# TM4C123GH6PM_1.net
KiCad netlist of a schematic drawn in Altium Designer
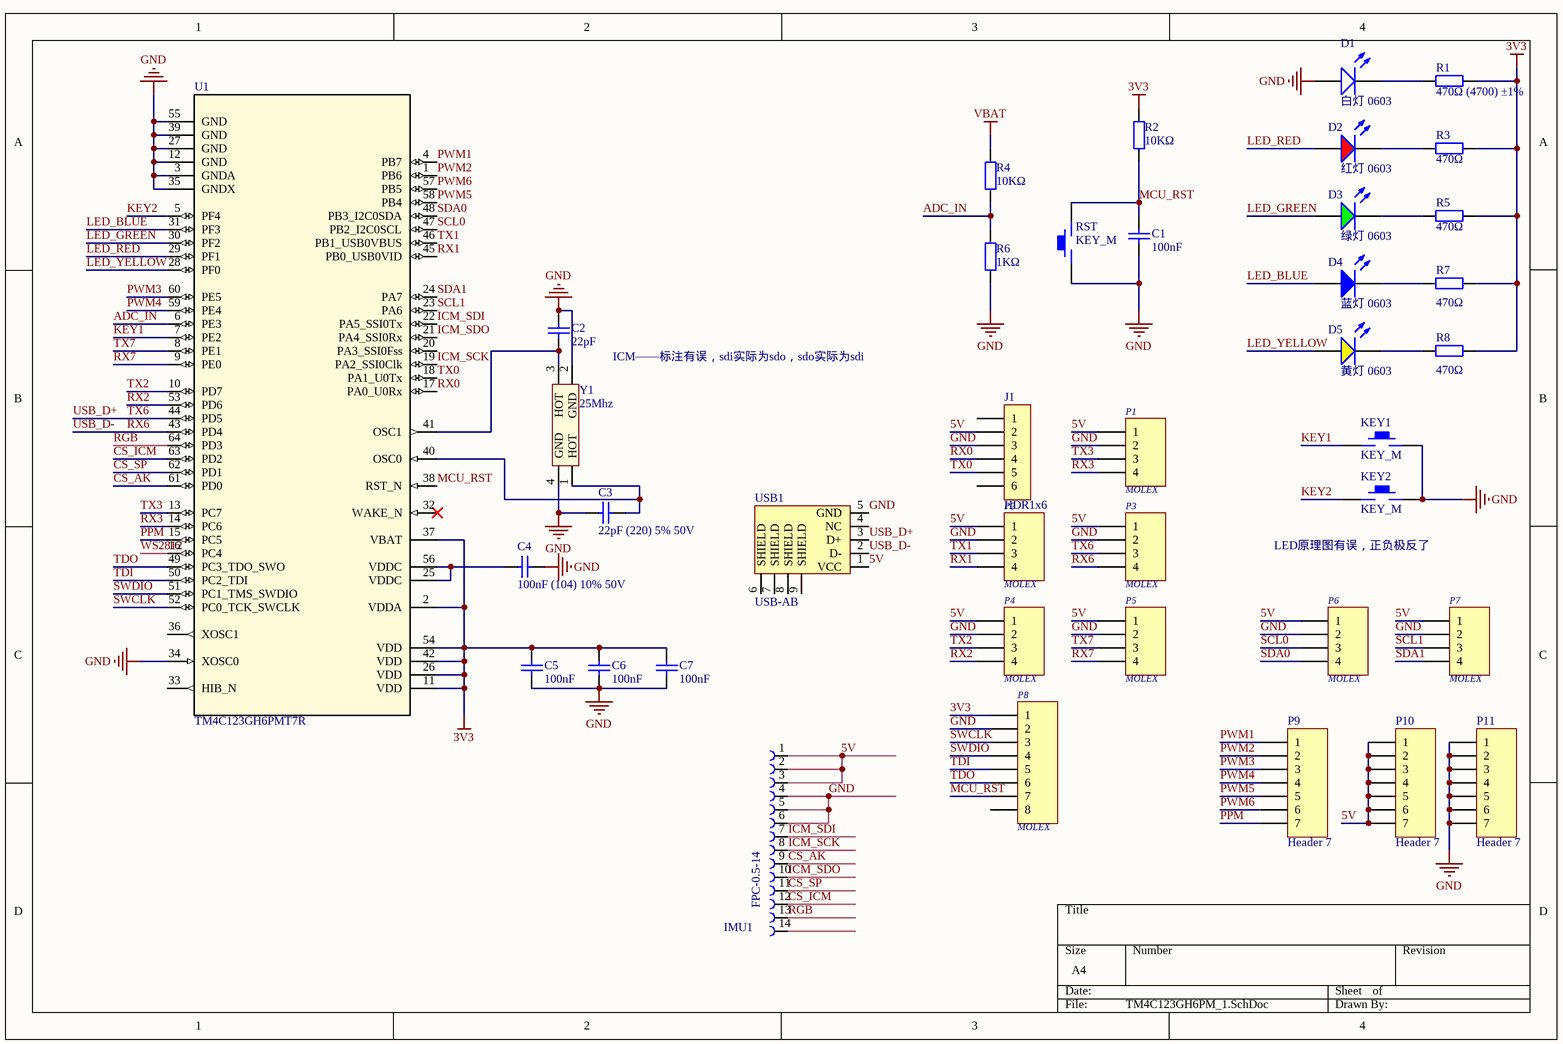
[diagram p0: TM4C123GH6PM_1.SchDoc]

(export (version "E")
  (design (tool "Eeschema 10.0.6"))
  (components
    (comp (ref "C1")
      (value "100nF")
      (footprint "0603_C")
      (description "贴片电容")
      (libsource (lib "Miscellaneous Devices LC") (part "0603 100nF (104) 10% 50V"))
    )
    (comp (ref "C2")
      (value "22pF")
      (footprint "0603_C")
      (description "贴片电容")
      (libsource (lib "Miscellaneous Devices LC") (part "0603 22pF (220) 5% 50V"))
    )
    (comp (ref "C3")
      (value "22pF (220) 5% 50V")
      (footprint "0603_C")
      (description "贴片电容")
      (libsource (lib "Miscellaneous Devices LC") (part "0603 22pF (220) 5% 50V"))
    )
    (comp (ref "C4")
      (value "100nF (104) 10% 50V")
      (footprint "0603_C")
      (description "贴片电容")
      (libsource (lib "Miscellaneous Devices LC") (part "0603 100nF (104) 10% 50V"))
    )
    (comp (ref "C5")
      (value "100nF")
      (footprint "0603_C")
      (description "贴片电容")
      (libsource (lib "Miscellaneous Devices LC") (part "0603 100nF (104) 10% 50V"))
    )
    (comp (ref "C6")
      (value "100nF")
      (footprint "0603_C")
      (description "贴片电容")
      (libsource (lib "Miscellaneous Devices LC") (part "0603 100nF (104) 10% 50V"))
    )
    (comp (ref "C7")
      (value "100nF")
      (footprint "0603_C")
      (description "贴片电容")
      (libsource (lib "Miscellaneous Devices LC") (part "0603 100nF (104) 10% 50V"))
    )
    (comp (ref "D1")
      (value "白灯 0603")
      (footprint "0603_LED_S1")
      (description "发光二极管")
      (libsource (lib "Miscellaneous Devices LC") (part "0603 白灯"))
    )
    (comp (ref "D2")
      (value "红灯 0603")
      (footprint "0603_LED_S1")
      (description "发光二极管")
      (libsource (lib "Miscellaneous Devices LC") (part "0603 红灯"))
    )
    (comp (ref "D3")
      (value "绿灯 0603")
      (footprint "0603_LED_S1")
      (description "发光二极管")
      (libsource (lib "Miscellaneous Devices LC") (part "0603 绿灯"))
    )
    (comp (ref "D4")
      (value "蓝灯 0603")
      (footprint "0603_LED_S1")
      (description "发光二极管")
      (libsource (lib "Miscellaneous Devices LC") (part "0603 蓝灯"))
    )
    (comp (ref "D5")
      (value "黄灯 0603")
      (footprint "0603_LED_S1")
      (description "发光二极管")
      (libsource (lib "Miscellaneous Devices LC") (part "0603 黄灯"))
    )
    (comp (ref "IMU1")
      (value "FPC-0.5-14")
      (footprint "FPC-0.5-14")
      (description "FFC / FPC Board Connector, WR-FPC Series, Surface Mount, Receptacle, 14, Bottom, 0.5 mm")
      (fields (field (name "MP") "687114149022") (field (name "MF") "Wurth Electronics"))
      (libsource (lib "MyLib") (part "FPC-0.5-14"))
    )
    (comp (ref "J1")
      (value "HDR1x6")
      (footprint "PIN-6-2.54-1.0")
      (description "Connector")
      (libsource (lib "MyLib") (part "HDR1x6"))
    )
    (comp (ref "KEY1")
      (value "KEY_M")
      (footprint "KEY_SOP3625")
      (libsource (lib "STM32F767核心板封装库") (part "KEY_M"))
    )
    (comp (ref "KEY2")
      (value "KEY_M")
      (footprint "KEY_SOP3625")
      (libsource (lib "STM32F767核心板封装库") (part "KEY_M"))
    )
    (comp (ref "P1")
      (value "MOLEX")
      (footprint "1.25 molex")
      (fields (field (name "PUBLISHER") "Altium Limited"))
      (libsource (lib "fly_smart") (part "Header 4"))
    )
    (comp (ref "P2")
      (value "MOLEX")
      (footprint "1.25 molex")
      (fields (field (name "PUBLISHER") "Altium Limited"))
      (libsource (lib "fly_smart") (part "Header 4"))
    )
    (comp (ref "P3")
      (value "MOLEX")
      (footprint "1.25 molex")
      (fields (field (name "PUBLISHER") "Altium Limited"))
      (libsource (lib "fly_smart") (part "Header 4"))
    )
    (comp (ref "P4")
      (value "MOLEX")
      (footprint "1.25 molex")
      (fields (field (name "PUBLISHER") "Altium Limited"))
      (libsource (lib "fly_smart") (part "Header 4"))
    )
    (comp (ref "P5")
      (value "MOLEX")
      (footprint "1.25 molex")
      (fields (field (name "PUBLISHER") "Altium Limited"))
      (libsource (lib "fly_smart") (part "Header 4"))
    )
    (comp (ref "P6")
      (value "MOLEX")
      (footprint "1.25 molex")
      (fields (field (name "PUBLISHER") "Altium Limited"))
      (libsource (lib "fly_smart") (part "Header 4"))
    )
    (comp (ref "P7")
      (value "MOLEX")
      (footprint "1.25 molex")
      (fields (field (name "PUBLISHER") "Altium Limited"))
      (libsource (lib "fly_smart") (part "Header 4"))
    )
    (comp (ref "P8")
      (value "MOLEX")
      (footprint "1.25 molex -8")
      (fields (field (name "PUBLISHER") "Altium Limited"))
      (libsource (lib "TM4C_Series") (part "Header 8"))
    )
    (comp (ref "P9")
      (value "Header 7")
      (footprint "HDR1X7")
      (description "Header, 7-Pin")
      (fields (field (name "PUBLISHER") "Altium Limited"))
      (libsource (lib "Miscellaneous Connectors") (part "Header 7"))
    )
    (comp (ref "P10")
      (value "Header 7")
      (footprint "HDR1X7")
      (description "Header, 7-Pin")
      (fields (field (name "PUBLISHER") "Altium Limited"))
      (libsource (lib "Miscellaneous Connectors") (part "Header 7"))
    )
    (comp (ref "P11")
      (value "Header 7")
      (footprint "HDR1X7")
      (description "Header, 7-Pin")
      (fields (field (name "PUBLISHER") "Altium Limited"))
      (libsource (lib "Miscellaneous Connectors") (part "Header 7"))
    )
    (comp (ref "R1")
      (value "470Ω (4700) ±1%")
      (footprint "0603_R")
      (description "贴片电阻")
      (libsource (lib "Miscellaneous Devices LC") (part "0603 470Ω (4700) 1%"))
    )
    (comp (ref "R2")
      (value "10KΩ")
      (footprint "0603_R")
      (description "贴片电阻")
      (libsource (lib "Miscellaneous Devices LC") (part "0603 10KΩ (1002) 1%"))
    )
    (comp (ref "R3")
      (value "470Ω")
      (footprint "0603_R")
      (description "贴片电阻")
      (libsource (lib "Miscellaneous Devices LC") (part "0603 470Ω (4700) 1%"))
    )
    (comp (ref "R4")
      (value "10KΩ")
      (footprint "0603_R")
      (description "贴片电阻")
      (libsource (lib "Miscellaneous Devices LC") (part "0603 10KΩ (1002) 1%"))
    )
    (comp (ref "R5")
      (value "470Ω")
      (footprint "0603_R")
      (description "贴片电阻")
      (libsource (lib "Miscellaneous Devices LC") (part "0603 470Ω (4700) 1%"))
    )
    (comp (ref "R6")
      (value "1KΩ")
      (footprint "0603_R")
      (description "贴片电阻")
      (libsource (lib "Miscellaneous Devices LC") (part "0603 1KΩ (1001) 1%"))
    )
    (comp (ref "R7")
      (value "470Ω")
      (footprint "0603_R")
      (description "贴片电阻")
      (libsource (lib "Miscellaneous Devices LC") (part "0603 470Ω (4700) 1%"))
    )
    (comp (ref "R8")
      (value "470Ω")
      (footprint "0603_R")
      (description "贴片电阻")
      (libsource (lib "Miscellaneous Devices LC") (part "0603 470Ω (4700) 1%"))
    )
    (comp (ref "RST") (value "KEY_M") (footprint "KEY_SOP3625") (libsource (lib "") (part "KEY_M_1")))
    (comp (ref "U1")
      (value "TM4C123GH6PMT7R")
      (footprint "PM0064A_M")
      (description "Imported")
      (fields
        (field (name "PARTNUMBER") "TM4C123GH6PMTR")
        (field (name "ALTERNATE_PARTNUMBER") "TM4C123GH6PMT")
      )
      (libsource (lib "TM4C123GH6PM") (part "TM4C123GH6PMT7R"))
    )
    (comp (ref "USB1")
      (value "USB-AB")
      (footprint "USB_AB - 5S - B")
      (description "MicroUSB")
      (libsource (lib "TM4C_Series") (part "USB-AB"))
    )
    (comp (ref "Y1")
      (value "25Mhz")
      (footprint "XTAL3225")
      (description "3225贴片无源晶振")
      (libsource (lib "TM4C123GH6PM") (part "XTAL_3225"))
    )
  )
  (nets
    (net (code "1") (name "/5V") (class "Default")
      (node (ref "IMU1") (pin "1") (pinfunction "14_1") (pintype "passive"))
      (node (ref "IMU1") (pin "2") (pinfunction "13_2") (pintype "passive"))
      (node (ref "IMU1") (pin "3") (pinfunction "12_3") (pintype "passive"))
      (node (ref "J1") (pin "2") (pinfunction "2_2") (pintype "passive"))
      (node (ref "P1") (pin "1") (pinfunction "1_1") (pintype "passive"))
      (node (ref "P10") (pin "1") (pinfunction "1_1") (pintype "passive"))
      (node (ref "P10") (pin "2") (pinfunction "2_2") (pintype "passive"))
      (node (ref "P10") (pin "3") (pinfunction "3_3") (pintype "passive"))
      (node (ref "P10") (pin "4") (pinfunction "4_4") (pintype "passive"))
      (node (ref "P10") (pin "5") (pinfunction "5_5") (pintype "passive"))
      (node (ref "P10") (pin "6") (pinfunction "6_6") (pintype "passive"))
      (node (ref "P10") (pin "7") (pinfunction "7_7") (pintype "passive"))
      (node (ref "P2") (pin "1") (pinfunction "1_1") (pintype "passive"))
      (node (ref "P3") (pin "1") (pinfunction "1_1") (pintype "passive"))
      (node (ref "P4") (pin "1") (pinfunction "1_1") (pintype "passive"))
      (node (ref "P5") (pin "1") (pinfunction "1_1") (pintype "passive"))
      (node (ref "P6") (pin "1") (pinfunction "1_1") (pintype "passive"))
      (node (ref "P7") (pin "1") (pinfunction "1_1") (pintype "passive"))
      (node (ref "USB1") (pin "1") (pinfunction "VCC_1") (pintype "passive"))
    )
    (net (code "2") (name "/ADC_IN") (class "Default")
      (node (ref "R4") (pin "1") (pinfunction "1_1") (pintype "passive"))
      (node (ref "R6") (pin "2") (pinfunction "2_2") (pintype "passive"))
      (node (ref "U1") (pin "6") (pinfunction "PE3_6") (pintype "bidirectional"))
    )
    (net (code "3") (name "/CS_AK") (class "Default")
      (node (ref "IMU1") (pin "9") (pinfunction "6_9") (pintype "passive"))
      (node (ref "U1") (pin "61") (pinfunction "PD0_61") (pintype "bidirectional"))
    )
    (net (code "4") (name "/CS_ICM") (class "Default")
      (node (ref "IMU1") (pin "12") (pinfunction "3_12") (pintype "passive"))
      (node (ref "U1") (pin "63") (pinfunction "PD2_63") (pintype "bidirectional"))
    )
    (net (code "5") (name "/CS_SP") (class "Default")
      (node (ref "IMU1") (pin "11") (pinfunction "4_11") (pintype "passive"))
      (node (ref "U1") (pin "62") (pinfunction "PD1_62") (pintype "bidirectional"))
    )
    (net (code "6") (name "/ICM_SCK") (class "Default")
      (node (ref "IMU1") (pin "8") (pinfunction "7_8") (pintype "passive"))
      (node (ref "U1") (pin "19") (pinfunction "PA2_SSI0Clk_19") (pintype "bidirectional"))
    )
    (net (code "7") (name "/ICM_SDI") (class "Default")
      (node (ref "IMU1") (pin "7") (pinfunction "8_7") (pintype "passive"))
      (node (ref "U1") (pin "22") (pinfunction "PA5_SSI0Tx_22") (pintype "bidirectional"))
    )
    (net (code "8") (name "/ICM_SDO") (class "Default")
      (node (ref "IMU1") (pin "10") (pinfunction "5_10") (pintype "passive"))
      (node (ref "U1") (pin "21") (pinfunction "PA4_SSI0Rx_21") (pintype "bidirectional"))
    )
    (net (code "9") (name "/KEY1") (class "Default")
      (node (ref "KEY1") (pin "1") (pinfunction "1_1") (pintype "passive"))
      (node (ref "U1") (pin "7") (pinfunction "PE2_7") (pintype "bidirectional"))
    )
    (net (code "10") (name "/KEY2") (class "Default")
      (node (ref "KEY2") (pin "1") (pinfunction "1_1") (pintype "passive"))
      (node (ref "U1") (pin "5") (pinfunction "PF4_5") (pintype "bidirectional"))
    )
    (net (code "11") (name "/LED_BLUE") (class "Default")
      (node (ref "D4") (pin "A") (pinfunction "A_A") (pintype "passive"))
      (node (ref "U1") (pin "31") (pinfunction "PF3_31") (pintype "bidirectional"))
    )
    (net (code "12") (name "/LED_GREEN") (class "Default")
      (node (ref "D3") (pin "A") (pinfunction "A_A") (pintype "passive"))
      (node (ref "U1") (pin "30") (pinfunction "PF2_30") (pintype "bidirectional"))
    )
    (net (code "13") (name "/LED_RED") (class "Default")
      (node (ref "D2") (pin "A") (pinfunction "A_A") (pintype "passive"))
      (node (ref "U1") (pin "29") (pinfunction "PF1_29") (pintype "bidirectional"))
    )
    (net (code "14") (name "/LED_YELLOW") (class "Default")
      (node (ref "D5") (pin "A") (pinfunction "A_A") (pintype "passive"))
      (node (ref "U1") (pin "28") (pinfunction "PF0_28") (pintype "bidirectional"))
    )
    (net (code "15") (name "/MCU_RST") (class "Default")
      (node (ref "C1") (pin "2") (pinfunction "2_2") (pintype "passive"))
      (node (ref "P8") (pin "7") (pinfunction "7_7") (pintype "passive"))
      (node (ref "R2") (pin "1") (pinfunction "1_1") (pintype "passive"))
      (node (ref "RST") (pin "2") (pinfunction "2_2") (pintype "passive"))
      (node (ref "U1") (pin "38") (pinfunction "RST_N_38") (pintype "input"))
    )
    (net (code "16") (name "/PPM") (class "Default")
      (node (ref "P9") (pin "7") (pinfunction "7_7") (pintype "passive"))
      (node (ref "U1") (pin "15") (pinfunction "PC5_15") (pintype "bidirectional"))
    )
    (net (code "17") (name "/PWM1") (class "Default")
      (node (ref "P9") (pin "1") (pinfunction "1_1") (pintype "passive"))
      (node (ref "U1") (pin "4") (pinfunction "PB7_4") (pintype "bidirectional"))
    )
    (net (code "18") (name "/PWM2") (class "Default")
      (node (ref "P9") (pin "2") (pinfunction "2_2") (pintype "passive"))
      (node (ref "U1") (pin "1") (pinfunction "PB6_1") (pintype "bidirectional"))
    )
    (net (code "19") (name "/PWM3") (class "Default")
      (node (ref "P9") (pin "3") (pinfunction "3_3") (pintype "passive"))
      (node (ref "U1") (pin "60") (pinfunction "PE5_60") (pintype "bidirectional"))
    )
    (net (code "20") (name "/PWM4") (class "Default")
      (node (ref "P9") (pin "4") (pinfunction "4_4") (pintype "passive"))
      (node (ref "U1") (pin "59") (pinfunction "PE4_59") (pintype "bidirectional"))
    )
    (net (code "21") (name "/PWM5") (class "Default")
      (node (ref "P9") (pin "5") (pinfunction "5_5") (pintype "passive"))
      (node (ref "U1") (pin "58") (pinfunction "PB4_58") (pintype "bidirectional"))
    )
    (net (code "22") (name "/PWM6") (class "Default")
      (node (ref "P9") (pin "6") (pinfunction "6_6") (pintype "passive"))
      (node (ref "U1") (pin "57") (pinfunction "PB5_57") (pintype "bidirectional"))
    )
    (net (code "23") (name "/RGB") (class "Default")
      (node (ref "IMU1") (pin "13") (pinfunction "2_13") (pintype "passive"))
      (node (ref "U1") (pin "64") (pinfunction "PD3_64") (pintype "bidirectional"))
    )
    (net (code "24") (name "/RX0") (class "Default")
      (node (ref "J1") (pin "4") (pinfunction "4_4") (pintype "passive"))
      (node (ref "U1") (pin "17") (pinfunction "PA0_U0Rx_17") (pintype "bidirectional"))
    )
    (net (code "25") (name "/RX1") (class "Default")
      (node (ref "P2") (pin "4") (pinfunction "4_4") (pintype "passive"))
      (node (ref "U1") (pin "45") (pinfunction "PB0_USB0VID_45") (pintype "bidirectional"))
    )
    (net (code "26") (name "/RX2") (class "Default")
      (node (ref "P4") (pin "4") (pinfunction "4_4") (pintype "passive"))
      (node (ref "U1") (pin "53") (pinfunction "PD6_53") (pintype "bidirectional"))
    )
    (net (code "27") (name "/RX3") (class "Default")
      (node (ref "P1") (pin "4") (pinfunction "4_4") (pintype "passive"))
      (node (ref "U1") (pin "14") (pinfunction "PC6_14") (pintype "bidirectional"))
    )
    (net (code "28") (name "/RX6") (class "Default")
      (node (ref "P3") (pin "4") (pinfunction "4_4") (pintype "passive"))
      (node (ref "U1") (pin "43") (pinfunction "PD4_43") (pintype "bidirectional"))
      (node (ref "USB1") (pin "2") (pinfunction "D-_2") (pintype "passive"))
    )
    (net (code "29") (name "/RX7") (class "Default")
      (node (ref "P5") (pin "4") (pinfunction "4_4") (pintype "passive"))
      (node (ref "U1") (pin "9") (pinfunction "PE0_9") (pintype "bidirectional"))
    )
    (net (code "30") (name "/SCL0") (class "Default")
      (node (ref "P6") (pin "3") (pinfunction "3_3") (pintype "passive"))
      (node (ref "U1") (pin "47") (pinfunction "PB2_I2C0SCL_47") (pintype "bidirectional"))
    )
    (net (code "31") (name "/SCL1") (class "Default")
      (node (ref "P7") (pin "3") (pinfunction "3_3") (pintype "passive"))
      (node (ref "U1") (pin "23") (pinfunction "PA6_23") (pintype "bidirectional"))
    )
    (net (code "32") (name "/SDA0") (class "Default")
      (node (ref "P6") (pin "4") (pinfunction "4_4") (pintype "passive"))
      (node (ref "U1") (pin "48") (pinfunction "PB3_I2C0SDA_48") (pintype "bidirectional"))
    )
    (net (code "33") (name "/SDA1") (class "Default")
      (node (ref "P7") (pin "4") (pinfunction "4_4") (pintype "passive"))
      (node (ref "U1") (pin "24") (pinfunction "PA7_24") (pintype "bidirectional"))
    )
    (net (code "34") (name "/SWCLK") (class "Default")
      (node (ref "P8") (pin "3") (pinfunction "3_3") (pintype "passive"))
      (node (ref "U1") (pin "52") (pinfunction "PC0_TCK_SWCLK_52") (pintype "bidirectional"))
    )
    (net (code "35") (name "/SWDIO") (class "Default")
      (node (ref "P8") (pin "4") (pinfunction "4_4") (pintype "passive"))
      (node (ref "U1") (pin "51") (pinfunction "PC1_TMS_SWDIO_51") (pintype "bidirectional"))
    )
    (net (code "36") (name "/TDI") (class "Default")
      (node (ref "P8") (pin "5") (pinfunction "5_5") (pintype "passive"))
      (node (ref "U1") (pin "50") (pinfunction "PC2_TDI_50") (pintype "bidirectional"))
    )
    (net (code "37") (name "/TDO") (class "Default")
      (node (ref "P8") (pin "6") (pinfunction "6_6") (pintype "passive"))
      (node (ref "U1") (pin "49") (pinfunction "PC3_TDO_SWO_49") (pintype "bidirectional"))
    )
    (net (code "38") (name "/TX0") (class "Default")
      (node (ref "J1") (pin "5") (pinfunction "5_5") (pintype "passive"))
      (node (ref "U1") (pin "18") (pinfunction "PA1_U0Tx_18") (pintype "bidirectional"))
    )
    (net (code "39") (name "/TX1") (class "Default")
      (node (ref "P2") (pin "3") (pinfunction "3_3") (pintype "passive"))
      (node (ref "U1") (pin "46") (pinfunction "PB1_USB0VBUS_46") (pintype "bidirectional"))
    )
    (net (code "40") (name "/TX2") (class "Default")
      (node (ref "P4") (pin "3") (pinfunction "3_3") (pintype "passive"))
      (node (ref "U1") (pin "10") (pinfunction "PD7_10") (pintype "bidirectional"))
    )
    (net (code "41") (name "/TX3") (class "Default")
      (node (ref "P1") (pin "3") (pinfunction "3_3") (pintype "passive"))
      (node (ref "U1") (pin "13") (pinfunction "PC7_13") (pintype "bidirectional"))
    )
    (net (code "42") (name "/TX6") (class "Default")
      (node (ref "P3") (pin "3") (pinfunction "3_3") (pintype "passive"))
      (node (ref "U1") (pin "44") (pinfunction "PD5_44") (pintype "bidirectional"))
      (node (ref "USB1") (pin "3") (pinfunction "D+_3") (pintype "passive"))
    )
    (net (code "43") (name "/TX7") (class "Default")
      (node (ref "P5") (pin "3") (pinfunction "3_3") (pintype "passive"))
      (node (ref "U1") (pin "8") (pinfunction "PE1_8") (pintype "bidirectional"))
    )
    (net (code "44") (name "/WS2812") (class "Default")
      (node (ref "U1") (pin "16") (pinfunction "PC4_16") (pintype "bidirectional"))
    )
    (net (code "45") (name "3V3") (class "Default")
      (node (ref "C5") (pin "2") (pinfunction "2_2") (pintype "passive"))
      (node (ref "C6") (pin "2") (pinfunction "2_2") (pintype "passive"))
      (node (ref "C7") (pin "2") (pinfunction "2_2") (pintype "passive"))
      (node (ref "P8") (pin "1") (pinfunction "1_1") (pintype "passive"))
      (node (ref "R1") (pin "2") (pinfunction "2_2") (pintype "passive"))
      (node (ref "R2") (pin "2") (pinfunction "2_2") (pintype "passive"))
      (node (ref "R3") (pin "2") (pinfunction "2_2") (pintype "passive"))
      (node (ref "R5") (pin "2") (pinfunction "2_2") (pintype "passive"))
      (node (ref "R7") (pin "2") (pinfunction "2_2") (pintype "passive"))
      (node (ref "R8") (pin "2") (pinfunction "2_2") (pintype "passive"))
      (node (ref "U1") (pin "11") (pinfunction "VDD_11") (pintype "power_in"))
      (node (ref "U1") (pin "2") (pinfunction "VDDA_2") (pintype "power_in"))
      (node (ref "U1") (pin "26") (pinfunction "VDD_26") (pintype "power_in"))
      (node (ref "U1") (pin "37") (pinfunction "VBAT_37") (pintype "power_in"))
      (node (ref "U1") (pin "42") (pinfunction "VDD_42") (pintype "power_in"))
      (node (ref "U1") (pin "54") (pinfunction "VDD_54") (pintype "power_in"))
    )
    (net (code "46") (name "GND") (class "Default")
      (node (ref "C1") (pin "1") (pinfunction "1_1") (pintype "passive"))
      (node (ref "C2") (pin "2") (pinfunction "2_2") (pintype "passive"))
      (node (ref "C3") (pin "2") (pinfunction "2_2") (pintype "passive"))
      (node (ref "C4") (pin "2") (pinfunction "2_2") (pintype "passive"))
      (node (ref "C5") (pin "1") (pinfunction "1_1") (pintype "passive"))
      (node (ref "C6") (pin "1") (pinfunction "1_1") (pintype "passive"))
      (node (ref "C7") (pin "1") (pinfunction "1_1") (pintype "passive"))
      (node (ref "D1") (pin "A") (pinfunction "A_A") (pintype "passive"))
      (node (ref "IMU1") (pin "4") (pinfunction "11_4") (pintype "passive"))
      (node (ref "IMU1") (pin "5") (pinfunction "10_5") (pintype "passive"))
      (node (ref "IMU1") (pin "6") (pinfunction "9_6") (pintype "passive"))
      (node (ref "J1") (pin "3") (pinfunction "3_3") (pintype "passive"))
      (node (ref "KEY1") (pin "2") (pinfunction "2_2") (pintype "passive"))
      (node (ref "KEY2") (pin "2") (pinfunction "2_2") (pintype "passive"))
      (node (ref "P1") (pin "2") (pinfunction "2_2") (pintype "passive"))
      (node (ref "P11") (pin "1") (pinfunction "1_1") (pintype "passive"))
      (node (ref "P11") (pin "2") (pinfunction "2_2") (pintype "passive"))
      (node (ref "P11") (pin "3") (pinfunction "3_3") (pintype "passive"))
      (node (ref "P11") (pin "4") (pinfunction "4_4") (pintype "passive"))
      (node (ref "P11") (pin "5") (pinfunction "5_5") (pintype "passive"))
      (node (ref "P11") (pin "6") (pinfunction "6_6") (pintype "passive"))
      (node (ref "P11") (pin "7") (pinfunction "7_7") (pintype "passive"))
      (node (ref "P2") (pin "2") (pinfunction "2_2") (pintype "passive"))
      (node (ref "P3") (pin "2") (pinfunction "2_2") (pintype "passive"))
      (node (ref "P4") (pin "2") (pinfunction "2_2") (pintype "passive"))
      (node (ref "P5") (pin "2") (pinfunction "2_2") (pintype "passive"))
      (node (ref "P6") (pin "2") (pinfunction "2_2") (pintype "passive"))
      (node (ref "P7") (pin "2") (pinfunction "2_2") (pintype "passive"))
      (node (ref "P8") (pin "2") (pinfunction "2_2") (pintype "passive"))
      (node (ref "R6") (pin "1") (pinfunction "1_1") (pintype "passive"))
      (node (ref "RST") (pin "1") (pinfunction "1_1") (pintype "passive"))
      (node (ref "U1") (pin "12") (pinfunction "GND_12") (pintype "power_in"))
      (node (ref "U1") (pin "27") (pinfunction "GND_27") (pintype "power_in"))
      (node (ref "U1") (pin "3") (pinfunction "GNDA_3") (pintype "power_in"))
      (node (ref "U1") (pin "34") (pinfunction "XOSC0_34") (pintype "input"))
      (node (ref "U1") (pin "35") (pinfunction "GNDX_35") (pintype "power_in"))
      (node (ref "U1") (pin "39") (pinfunction "GND_39") (pintype "power_in"))
      (node (ref "U1") (pin "55") (pinfunction "GND_55") (pintype "power_in"))
      (node (ref "USB1") (pin "5") (pinfunction "GND_5") (pintype "passive"))
      (node (ref "Y1") (pin "2") (pinfunction "GND_2") (pintype "passive"))
      (node (ref "Y1") (pin "4") (pinfunction "GND_4") (pintype "passive"))
    )
    (net (code "47") (name "Net-(C4-Pad1)") (class "Default")
      (node (ref "C4") (pin "1") (pinfunction "1_1") (pintype "passive"))
      (node (ref "U1") (pin "25") (pinfunction "VDDC_25") (pintype "power_in"))
      (node (ref "U1") (pin "56") (pinfunction "VDDC_56") (pintype "power_in"))
    )
    (net (code "48") (name "Net-(D1-PadK)") (class "Default")
      (node (ref "D1") (pin "K") (pinfunction "K_K") (pintype "passive"))
      (node (ref "R1") (pin "1") (pinfunction "1_1") (pintype "passive"))
    )
    (net (code "49") (name "Net-(D2-PadK)") (class "Default")
      (node (ref "D2") (pin "K") (pinfunction "K_K") (pintype "passive"))
      (node (ref "R3") (pin "1") (pinfunction "1_1") (pintype "passive"))
    )
    (net (code "50") (name "Net-(D3-PadK)") (class "Default")
      (node (ref "D3") (pin "K") (pinfunction "K_K") (pintype "passive"))
      (node (ref "R5") (pin "1") (pinfunction "1_1") (pintype "passive"))
    )
    (net (code "51") (name "Net-(D4-PadK)") (class "Default")
      (node (ref "D4") (pin "K") (pinfunction "K_K") (pintype "passive"))
      (node (ref "R7") (pin "1") (pinfunction "1_1") (pintype "passive"))
    )
    (net (code "52") (name "Net-(D5-PadK)") (class "Default")
      (node (ref "D5") (pin "K") (pinfunction "K_K") (pintype "passive"))
      (node (ref "R8") (pin "1") (pinfunction "1_1") (pintype "passive"))
    )
    (net (code "53") (name "Net-(U1-OSC0)") (class "Default")
      (node (ref "C3") (pin "1") (pinfunction "1_1") (pintype "passive"))
      (node (ref "U1") (pin "40") (pinfunction "OSC0_40") (pintype "input"))
      (node (ref "Y1") (pin "1") (pinfunction "HOT_1") (pintype "passive"))
    )
    (net (code "54") (name "Net-(U1-OSC1)") (class "Default")
      (node (ref "C2") (pin "1") (pinfunction "1_1") (pintype "passive"))
      (node (ref "U1") (pin "41") (pinfunction "OSC1_41") (pintype "output"))
      (node (ref "Y1") (pin "3") (pinfunction "HOT_3") (pintype "passive"))
    )
    (net (code "55") (name "VBAT") (class "Default")
      (node (ref "R4") (pin "2") (pinfunction "2_2") (pintype "passive"))
    )
    (net (code "56") (name "unconnected-(IMU1-1-Pad14)") (class "Default")
      (node (ref "IMU1") (pin "14") (pinfunction "1_14") (pintype "passive"))
    )
    (net (code "57") (name "unconnected-(J1-Pad1)") (class "Default")
      (node (ref "J1") (pin "1") (pinfunction "1_1") (pintype "passive"))
    )
    (net (code "58") (name "unconnected-(J1-Pad6)") (class "Default")
      (node (ref "J1") (pin "6") (pinfunction "6_6") (pintype "passive"))
    )
    (net (code "59") (name "unconnected-(P8-Pad8)") (class "Default")
      (node (ref "P8") (pin "8") (pinfunction "8_8") (pintype "passive"))
    )
    (net (code "60") (name "unconnected-(U1-HIB_N-Pad33)") (class "Default")
      (node (ref "U1") (pin "33") (pinfunction "HIB_N_33") (pintype "output"))
    )
    (net (code "61") (name "unconnected-(U1-PA3_SSI0Fss-Pad20)") (class "Default")
      (node (ref "U1") (pin "20") (pinfunction "PA3_SSI0Fss_20") (pintype "bidirectional"))
    )
    (net (code "62") (name "unconnected-(U1-WAKE_N-Pad32)") (class "Default")
      (node (ref "U1") (pin "32") (pinfunction "WAKE_N_32") (pintype "input+no_connect"))
    )
    (net (code "63") (name "unconnected-(U1-XOSC1-Pad36)") (class "Default")
      (node (ref "U1") (pin "36") (pinfunction "XOSC1_36") (pintype "output"))
    )
    (net (code "64") (name "unconnected-(USB1-NC-Pad4)") (class "Default")
      (node (ref "USB1") (pin "4") (pinfunction "NC_4") (pintype "passive"))
    )
    (net (code "65") (name "unconnected-(USB1-SHIELD-Pad6)") (class "Default")
      (node (ref "USB1") (pin "6") (pinfunction "SHIELD_6") (pintype "passive"))
    )
    (net (code "66") (name "unconnected-(USB1-SHIELD-Pad7)") (class "Default")
      (node (ref "USB1") (pin "7") (pinfunction "SHIELD_7") (pintype "passive"))
    )
    (net (code "67") (name "unconnected-(USB1-SHIELD-Pad8)") (class "Default")
      (node (ref "USB1") (pin "8") (pinfunction "SHIELD_8") (pintype "passive"))
    )
    (net (code "68") (name "unconnected-(USB1-SHIELD-Pad9)") (class "Default")
      (node (ref "USB1") (pin "9") (pinfunction "SHIELD_9") (pintype "passive"))
    )
  )
)
